# Schema1.net
KiCad netlist of a schematic drawn in EAGLE
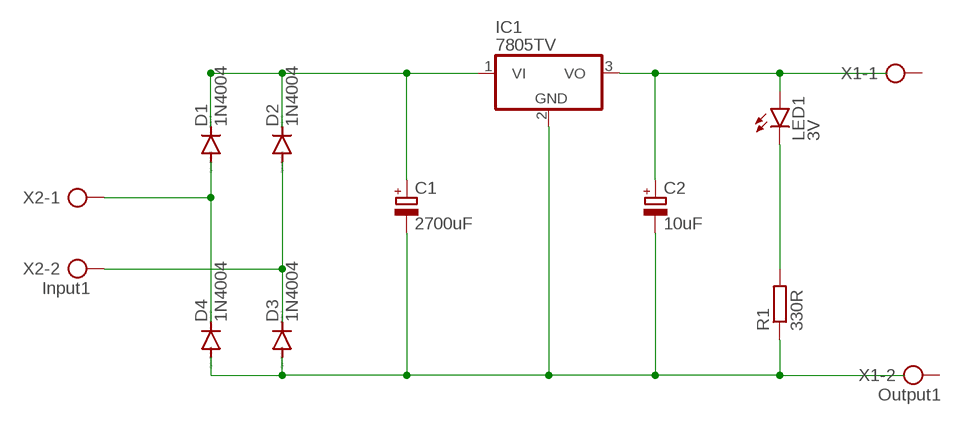
[diagram p0: schematic, sheet 1]

(export (version "E")
  (design (tool "Eeschema 10.0.6"))
  (components
    (comp (ref "C1")
      (value "2700uF")
      (footprint "eagle-import:EB20D")
      (libsource (lib "eagle-import") (part "CPOL-EUE10-20"))
    )
    (comp (ref "C2")
      (value "10uF")
      (footprint "eagle-import:E2,5-6E")
      (libsource (lib "eagle-import") (part "CPOL-EUE2,5-6E"))
    )
    (comp (ref "D1")
      (value "1N4004")
      (footprint "eagle-import:DO41-10")
      (libsource (lib "eagle-import") (part "1N4004"))
    )
    (comp (ref "D2")
      (value "1N4004")
      (footprint "eagle-import:DO41-10")
      (libsource (lib "eagle-import") (part "1N4004"))
    )
    (comp (ref "D3")
      (value "1N4004")
      (footprint "eagle-import:DO41-10")
      (libsource (lib "eagle-import") (part "1N4004"))
    )
    (comp (ref "D4")
      (value "1N4004")
      (footprint "eagle-import:DO41-10")
      (libsource (lib "eagle-import") (part "1N4004"))
    )
    (comp (ref "IC1")
      (value "7805TV")
      (footprint "eagle-import:TO220V")
      (libsource (lib "eagle-import") (part "78TV05"))
    )
    (comp (ref "LED1")
      (value "3V")
      (footprint "eagle-import:LED3MM")
      (libsource (lib "eagle-import") (part "LED3MM"))
    )
    (comp (ref "R1")
      (value "330R")
      (footprint "eagle-import:0309_10")
      (libsource (lib "eagle-import") (part "R-EU_0309/10"))
    )
    (comp (ref "X1")
      (value "Output1")
      (footprint "eagle-import:AK500_2-H")
      (libsource (lib "eagle-import") (part "AK500/2-H"))
    )
    (comp (ref "X2")
      (value "Input1")
      (footprint "eagle-import:AK500_2-H")
      (libsource (lib "eagle-import") (part "AK500/2-H"))
    )
  )
  (nets
    (net (code "1") (name "Net-(IC1-GND)") (class "Default")
      (node (ref "C1") (pin "-") (pinfunction "-_-") (pintype "passive"))
      (node (ref "C2") (pin "-") (pinfunction "-_-") (pintype "passive"))
      (node (ref "D3") (pin "A") (pinfunction "A_A") (pintype "passive"))
      (node (ref "D4") (pin "A") (pinfunction "A_A") (pintype "passive"))
      (node (ref "IC1") (pin "2") (pinfunction "GND_2") (pintype "passive"))
      (node (ref "R1") (pin "1") (pinfunction "1_1") (pintype "passive"))
    )
    (net (code "2") (name "Net-(IC1-VI)") (class "Default")
      (node (ref "C1") (pin "+") (pinfunction "+_+") (pintype "passive"))
      (node (ref "D1") (pin "C") (pinfunction "C_C") (pintype "passive"))
      (node (ref "D2") (pin "C") (pinfunction "C_C") (pintype "passive"))
      (node (ref "IC1") (pin "1") (pinfunction "VI_1") (pintype "input"))
    )
    (net (code "3") (name "Net-(IC1-VO)") (class "Default")
      (node (ref "C2") (pin "+") (pinfunction "+_+") (pintype "passive"))
      (node (ref "IC1") (pin "3") (pinfunction "VO_3") (pintype "passive"))
      (node (ref "LED1") (pin "A") (pinfunction "A_A") (pintype "passive"))
    )
    (net (code "4") (name "Net-(LED1-C)") (class "Default")
      (node (ref "LED1") (pin "K") (pinfunction "C_K") (pintype "passive"))
      (node (ref "R1") (pin "2") (pinfunction "2_2") (pintype "passive"))
    )
    (net (code "5") (name "Net-(X2A-KL)") (class "Default")
      (node (ref "D1") (pin "A") (pinfunction "A_A") (pintype "passive"))
      (node (ref "D4") (pin "C") (pinfunction "C_C") (pintype "passive"))
      (node (ref "X2") (pin "1") (pinfunction "KL_1") (pintype "passive"))
    )
    (net (code "6") (name "Net-(X2B-KL)") (class "Default")
      (node (ref "D2") (pin "A") (pinfunction "A_A") (pintype "passive"))
      (node (ref "D3") (pin "C") (pinfunction "C_C") (pintype "passive"))
      (node (ref "X2") (pin "2") (pinfunction "KL_2") (pintype "passive"))
    )
    (net (code "7") (name "unconnected-(X1A-KL-Pad1)") (class "Default")
      (node (ref "X1") (pin "1") (pinfunction "KL_1") (pintype "passive"))
    )
    (net (code "8") (name "unconnected-(X1B-KL-Pad2)") (class "Default")
      (node (ref "X1") (pin "2") (pinfunction "KL_2") (pintype "passive"))
    )
  )
)
